# ATtiny85_Temperature_Sensor.net
KiCad netlist of a schematic drawn in EAGLE
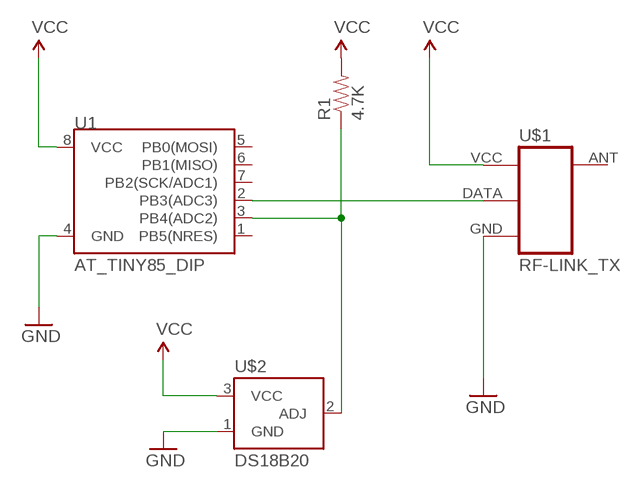
[diagram p0: schematic, sheet 1]

(export (version "E")
  (design (tool "Eeschema 10.0.6"))
  (components
    (comp (ref "R1")
      (value "4.7K")
      (footprint "eagle-import:AXIAL-0.3")
      (libsource (lib "eagle-import") (part "RESISTORAXIAL-0.3"))
    )
    (comp (ref "U$1")
      (value "RF-LINK_TX")
      (footprint "eagle-import:RF-LINK_TX")
      (libsource (lib "eagle-import") (part "RF-LINK_TX"))
    )
    (comp (ref "U$2")
      (value "DS18B20")
      (footprint "eagle-import:TO-92")
      (libsource (lib "eagle-import") (part "TEMPERATURE-SENSOR"))
    )
    (comp (ref "U1")
      (value "AT_TINY85_DIP")
      (footprint "eagle-import:DIP08")
      (libsource (lib "eagle-import") (part "ATTINY45TINY45-20-DIP"))
    )
  )
  (nets
    (net (code "1") (name "GND") (class "Default")
      (node (ref "U$1") (pin "GND") (pinfunction "GND_GND") (pintype "power_in"))
      (node (ref "U$2") (pin "1") (pinfunction "GND_1") (pintype "bidirectional"))
      (node (ref "U1") (pin "4") (pinfunction "GND_4") (pintype "bidirectional"))
    )
    (net (code "2") (name "Net-(R1-1)") (class "Default")
      (node (ref "R1") (pin "P$1") (pinfunction "1_P$1") (pintype "passive"))
      (node (ref "U$2") (pin "2") (pinfunction "ADJ_2") (pintype "bidirectional"))
      (node (ref "U1") (pin "3") (pinfunction "PB4(ADC2)_3") (pintype "bidirectional"))
    )
    (net (code "3") (name "Net-(U1-PB3(ADC3))") (class "Default")
      (node (ref "U$1") (pin "DATA") (pinfunction "DATA_DATA") (pintype "input"))
      (node (ref "U1") (pin "2") (pinfunction "PB3(ADC3)_2") (pintype "bidirectional"))
    )
    (net (code "4") (name "VCC") (class "Default")
      (node (ref "R1") (pin "P$2") (pinfunction "2_P$2") (pintype "passive"))
      (node (ref "U$1") (pin "VCC") (pinfunction "+5V_VCC") (pintype "power_in"))
      (node (ref "U$2") (pin "3") (pinfunction "VCC_3") (pintype "bidirectional"))
      (node (ref "U1") (pin "8") (pinfunction "VCC_8") (pintype "bidirectional"))
    )
    (net (code "5") (name "unconnected-(U$1-PadANT)") (class "Default")
      (node (ref "U$1") (pin "ANT") (pinfunction "ANT_ANT") (pintype "passive"))
    )
    (net (code "6") (name "unconnected-(U1-PB0(MOSI)-Pad5)") (class "Default")
      (node (ref "U1") (pin "5") (pinfunction "PB0(MOSI)_5") (pintype "bidirectional"))
    )
    (net (code "7") (name "unconnected-(U1-PB1(MISO)-Pad6)") (class "Default")
      (node (ref "U1") (pin "6") (pinfunction "PB1(MISO)_6") (pintype "bidirectional"))
    )
    (net (code "8") (name "unconnected-(U1-PB2(SCK{slash}ADC1)-Pad7)") (class "Default")
      (node (ref "U1") (pin "7") (pinfunction "PB2(SCK/ADC1)_7") (pintype "bidirectional"))
    )
    (net (code "9") (name "unconnected-(U1-PB5(NRES)-Pad1)") (class "Default")
      (node (ref "U1") (pin "1") (pinfunction "PB5(NRES)_1") (pintype "bidirectional"))
    )
  )
)
